# rover.net
KiCad netlist of a schematic drawn in EAGLE
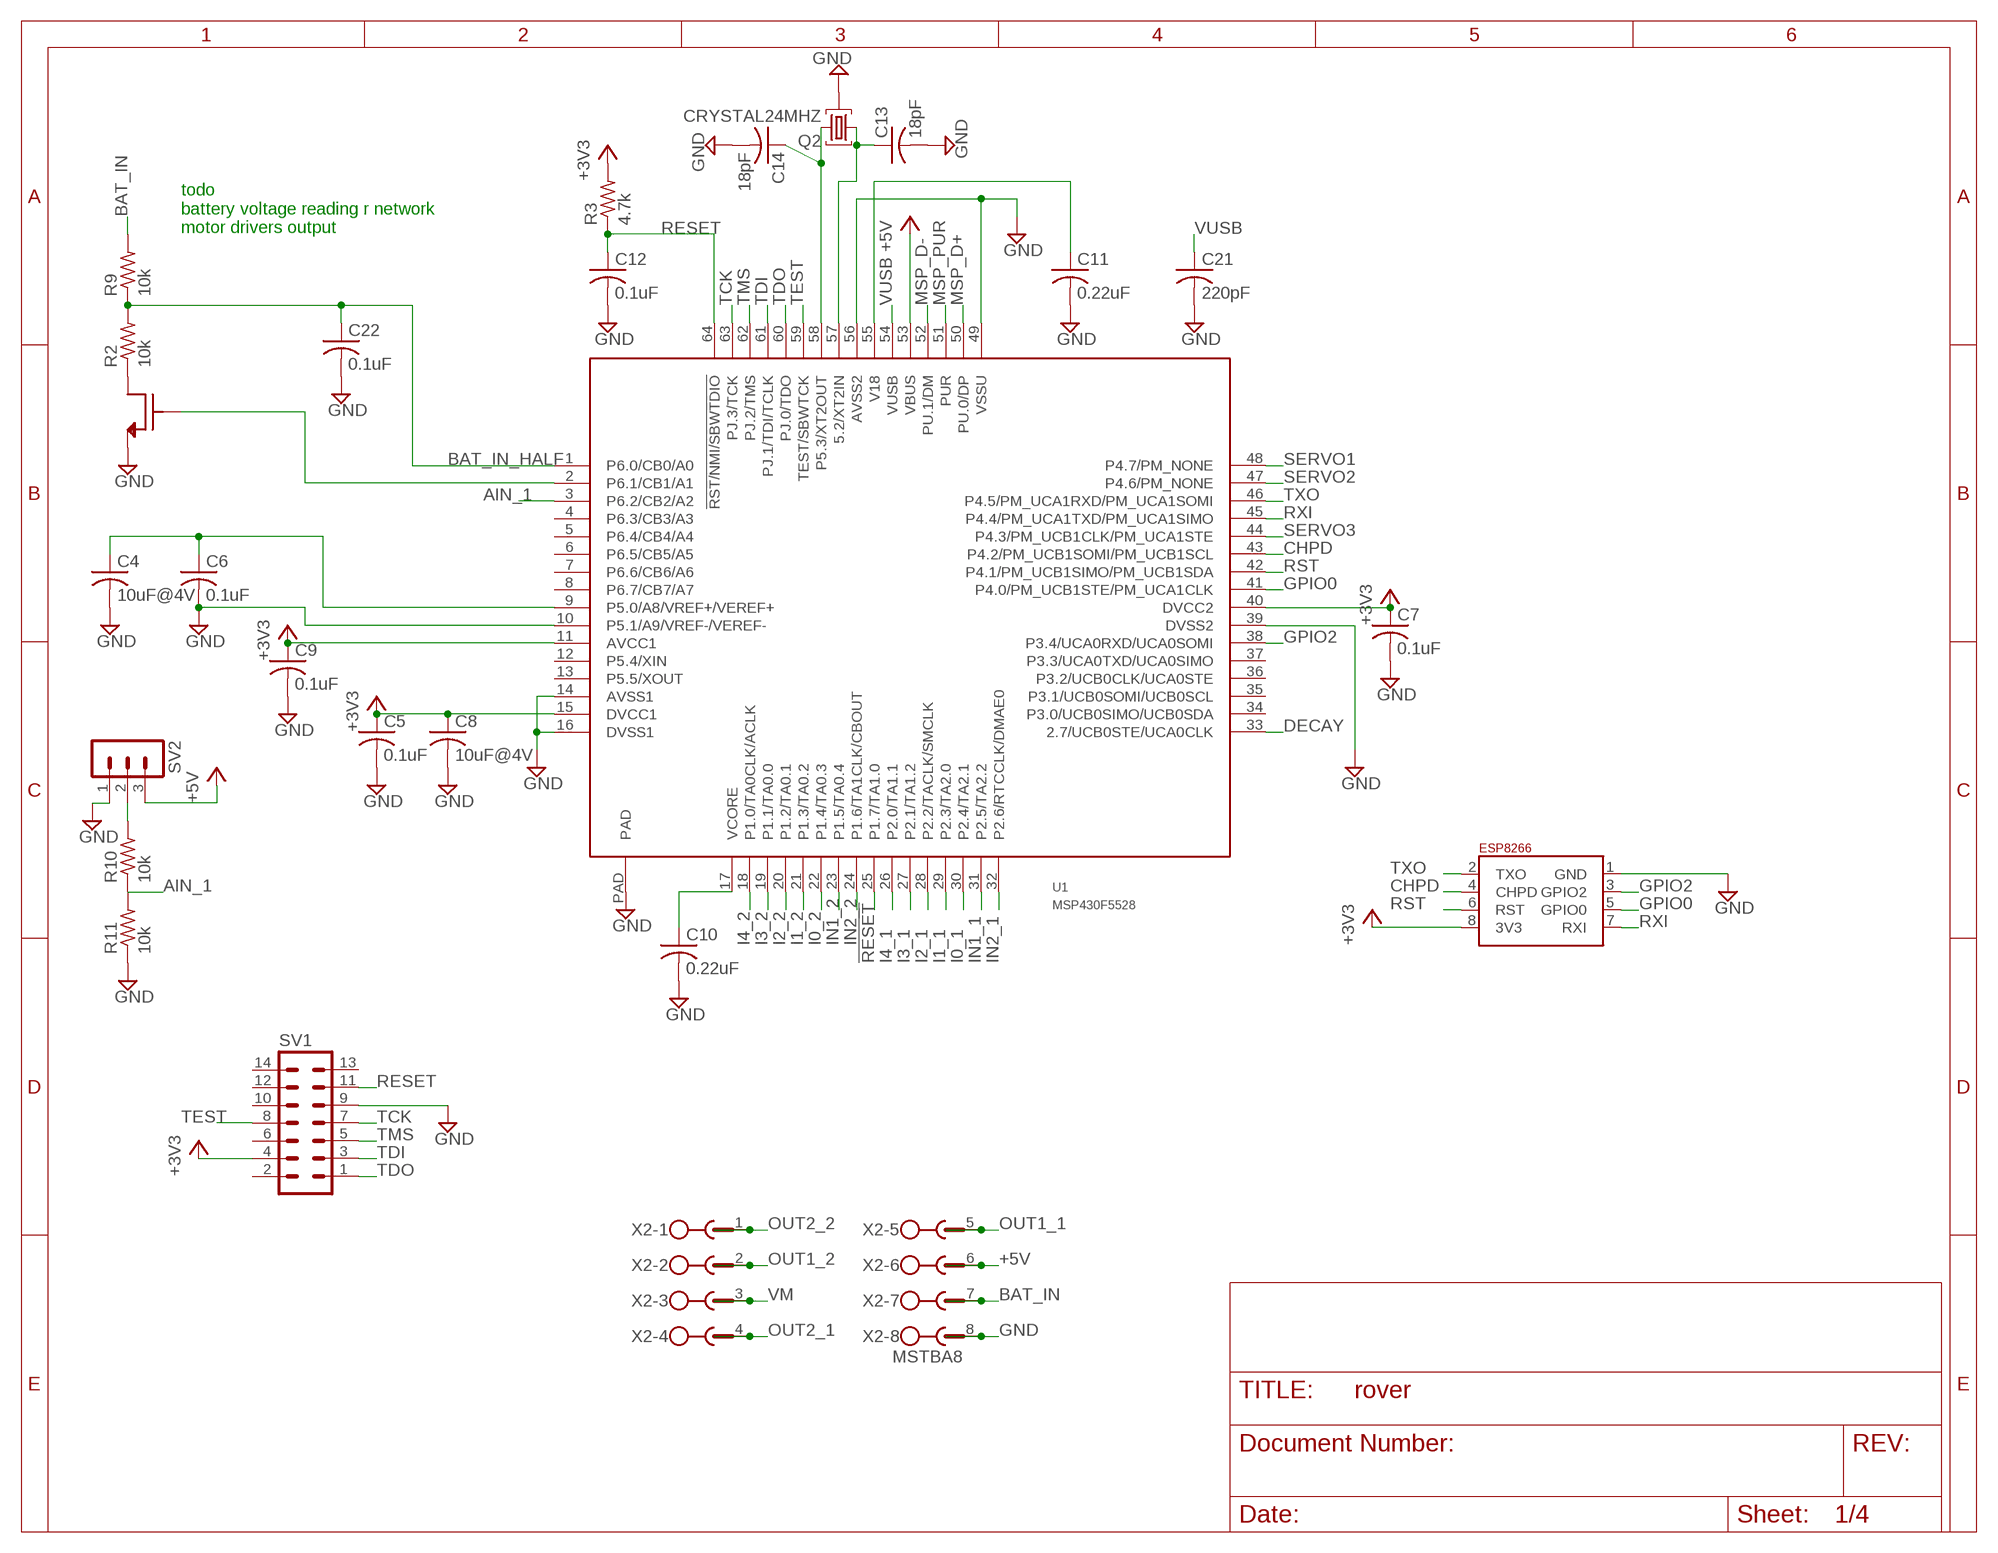
[diagram p0: schematic, sheet 1]
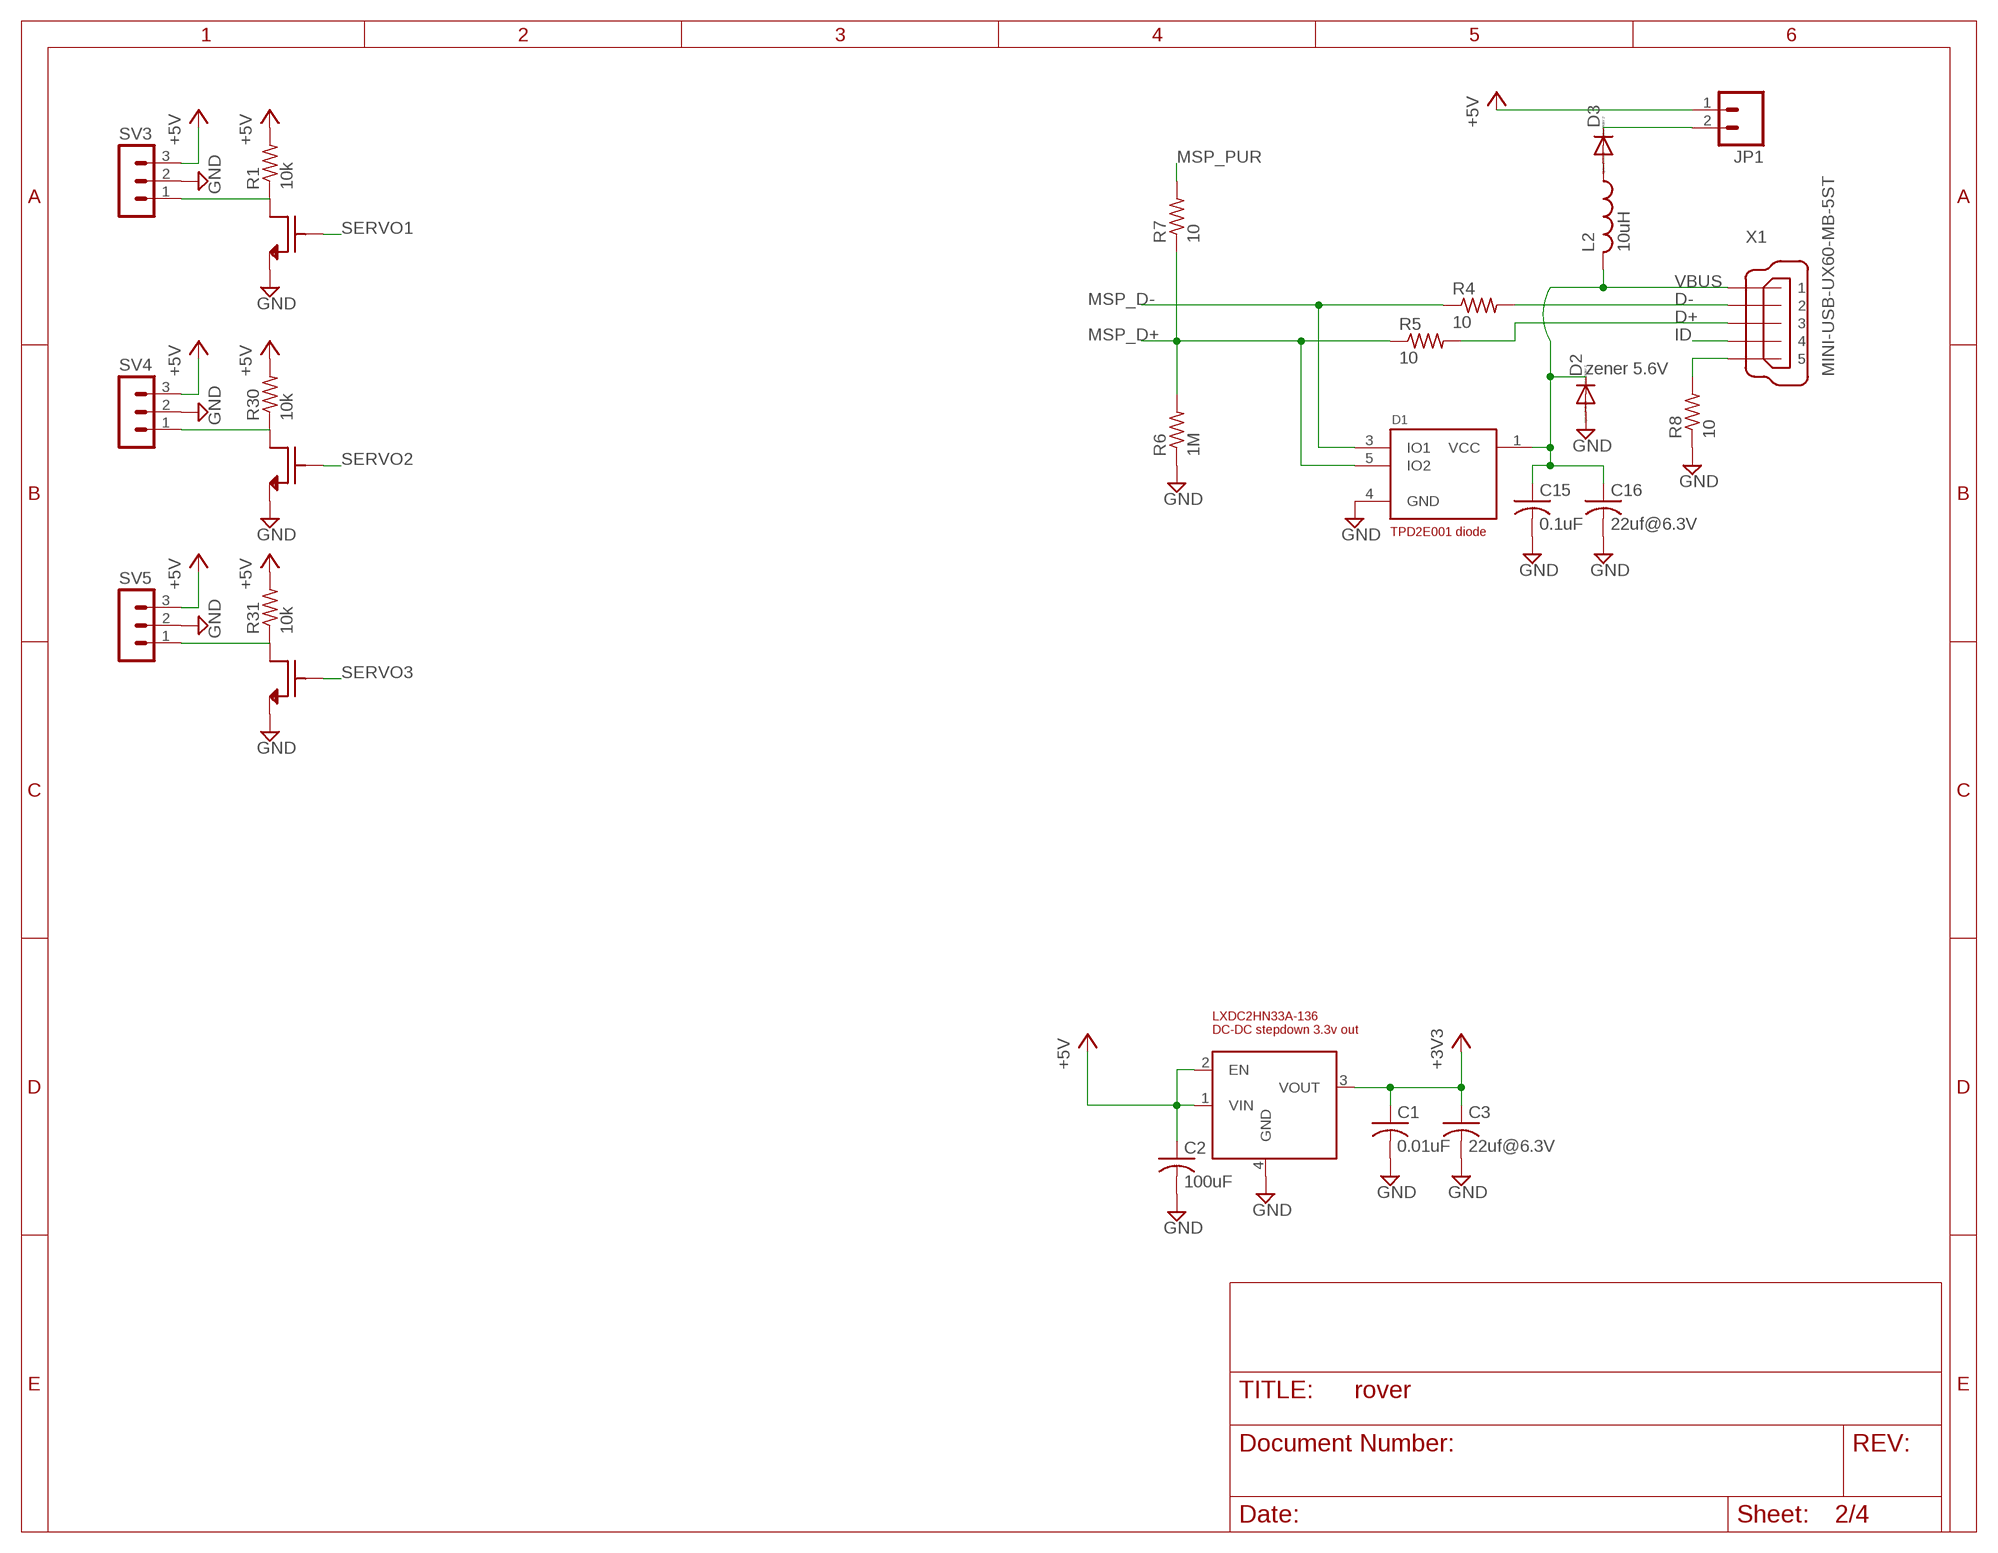
[diagram p1: schematic, sheet 2]
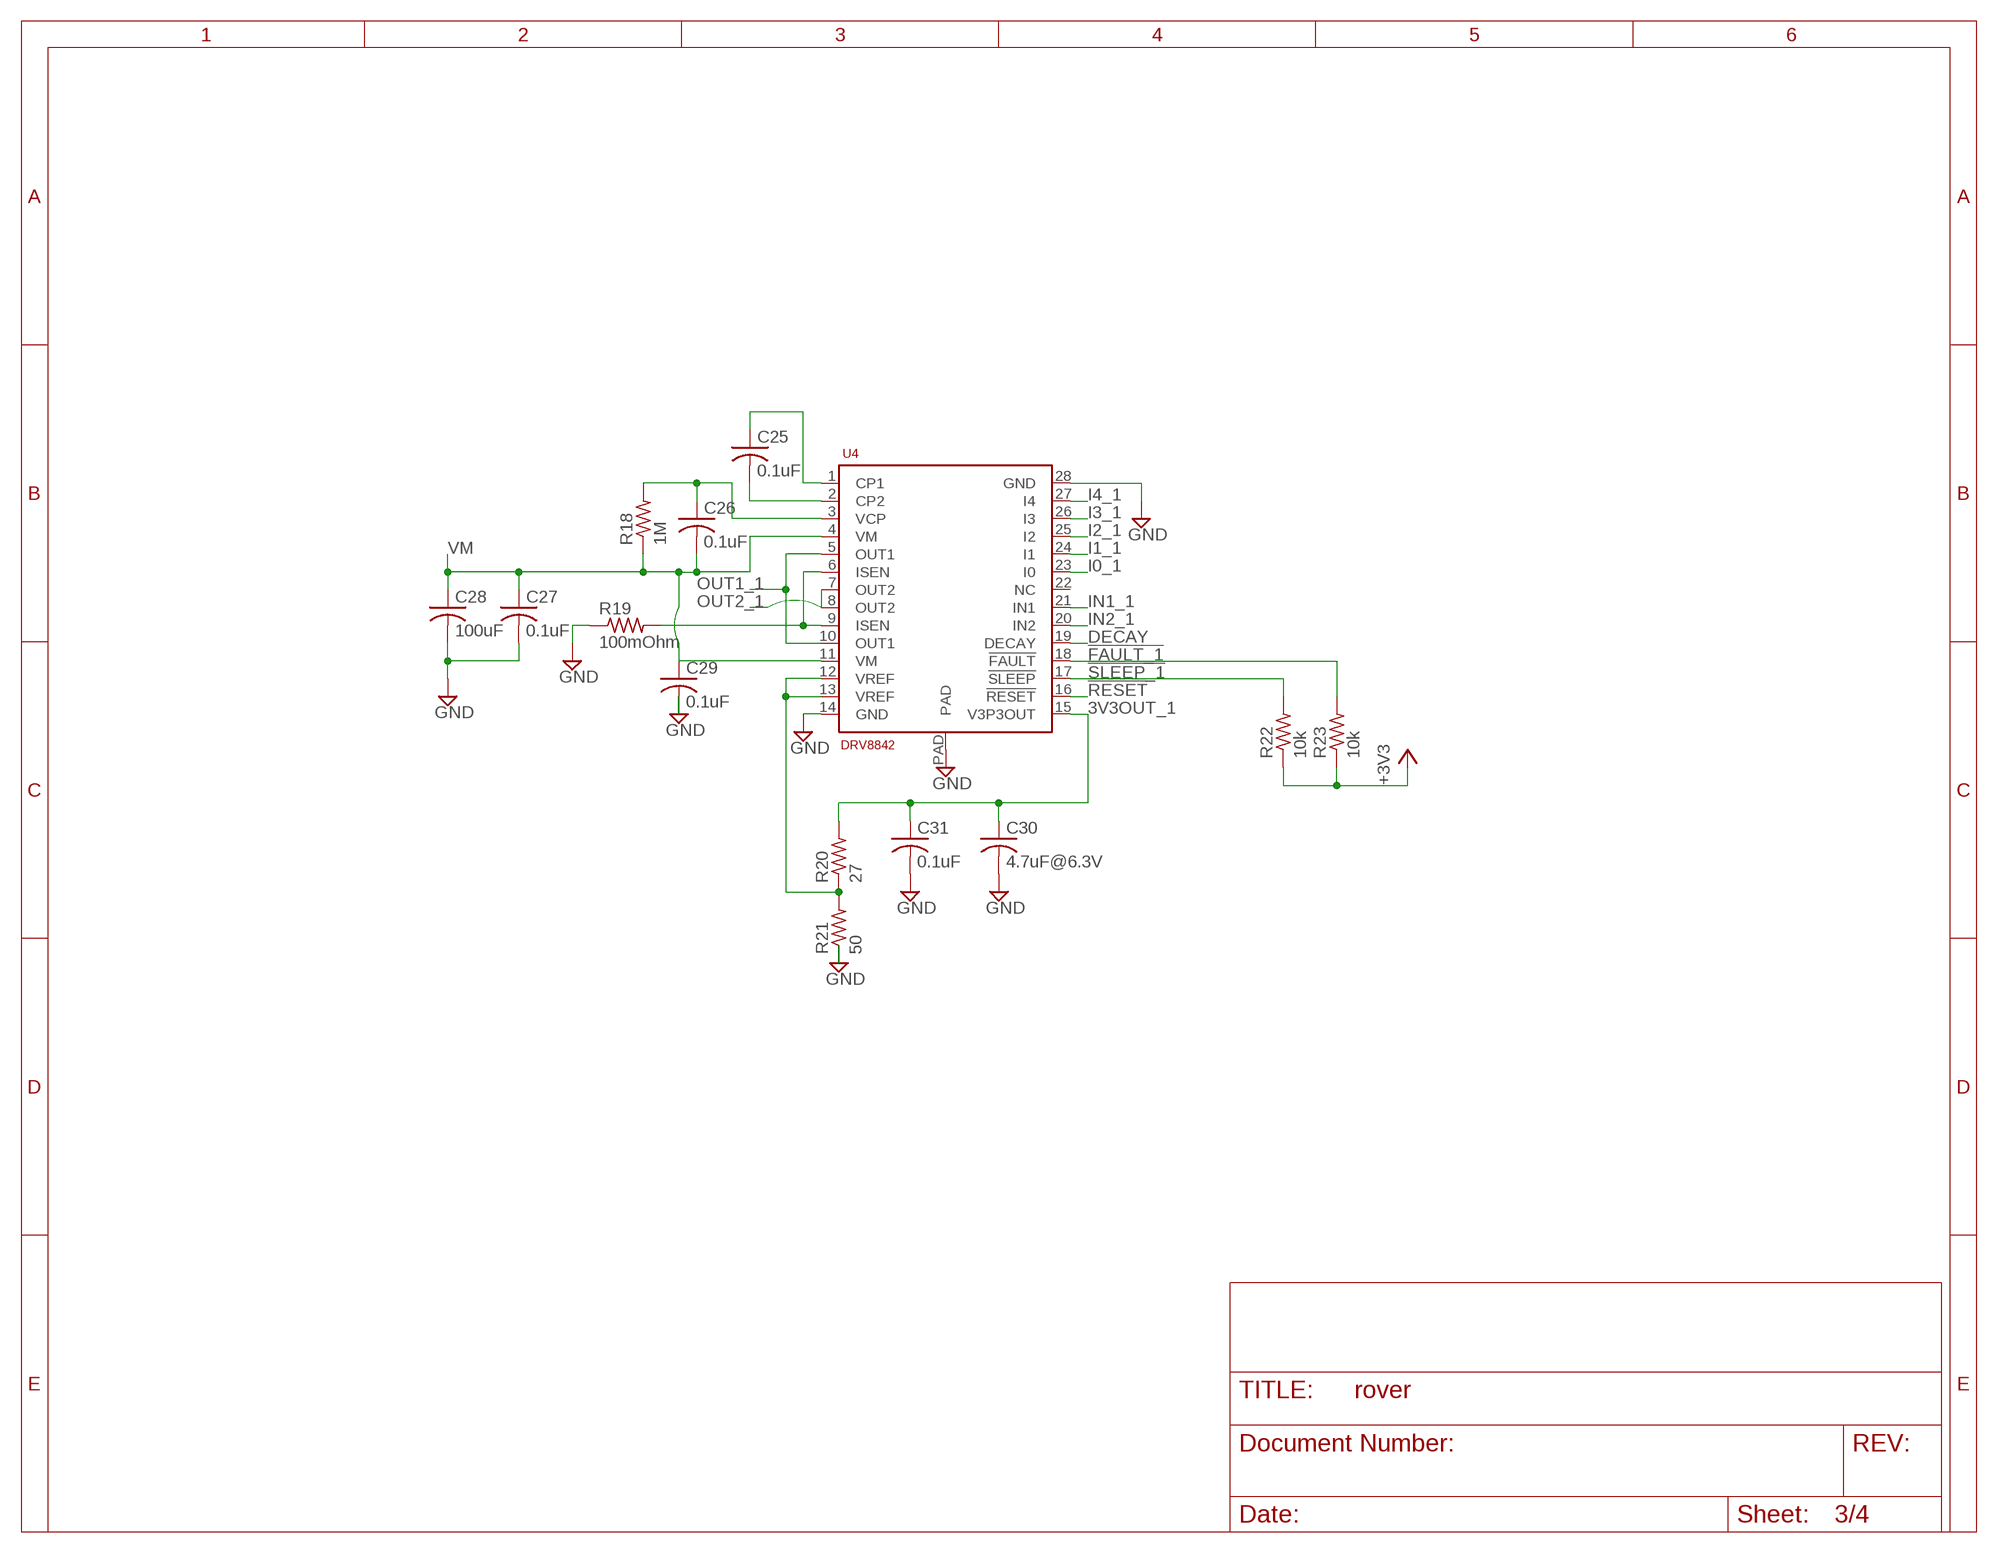
[diagram p2: schematic, sheet 3]
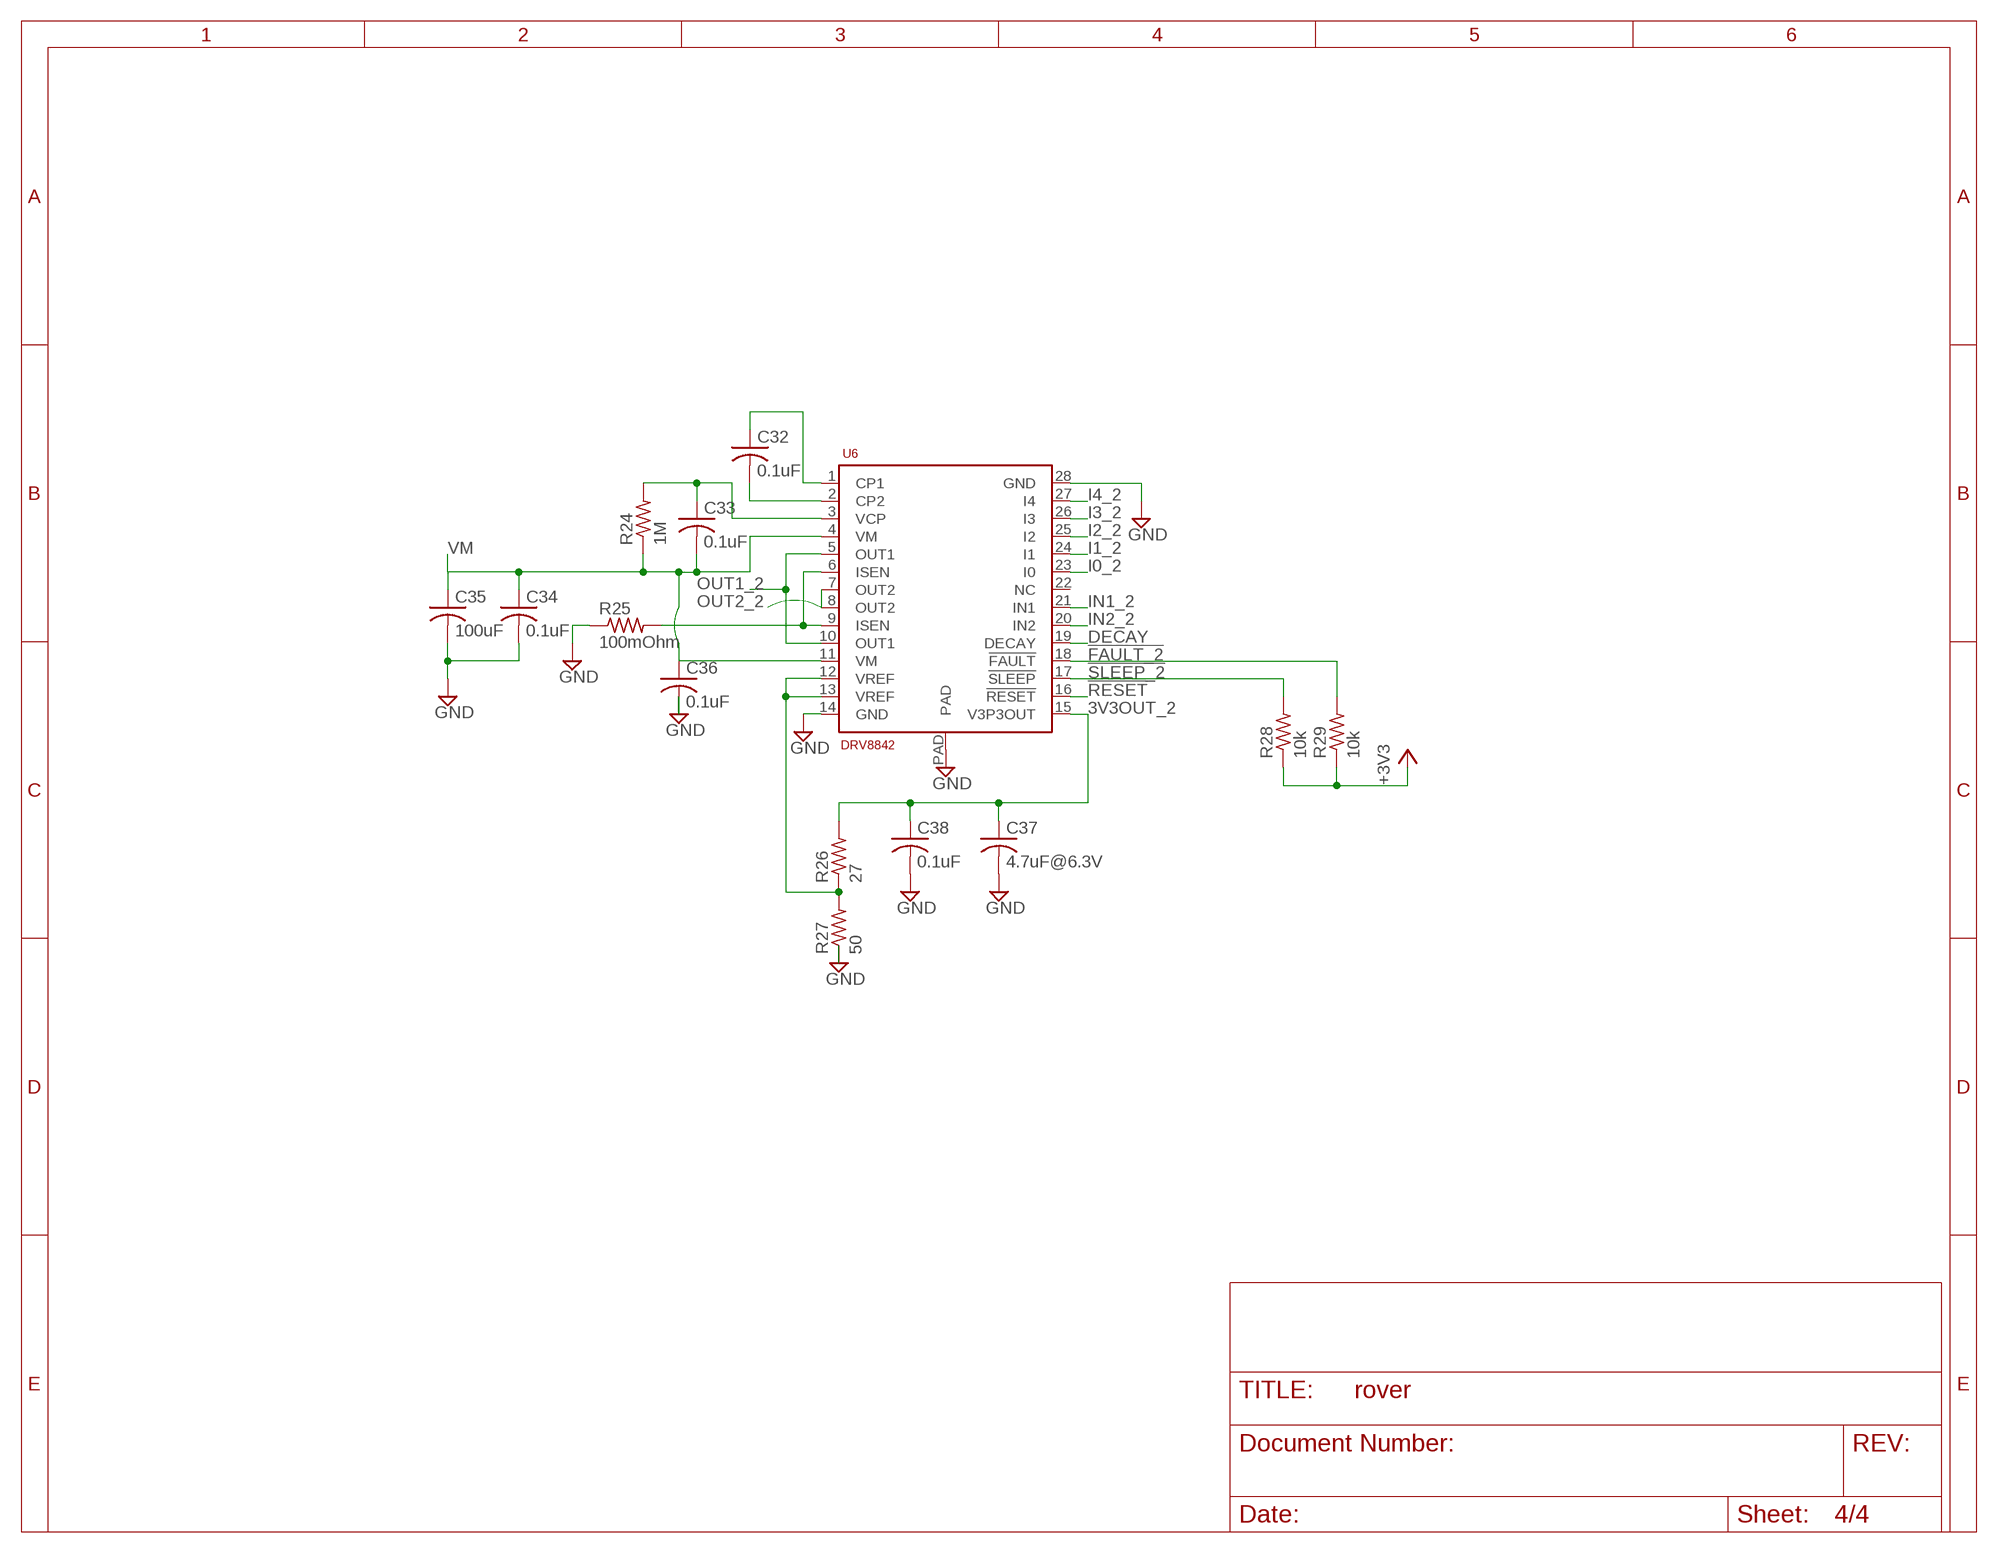
[diagram p3: schematic, sheet 4]

(export (version "E")
  (design (tool "Eeschema 10.0.6"))
  (components
    (comp (ref "C1")
      (value "0.01uF")
      (footprint "eagle-import:C0603")
      (fields (field (name "MFG") "murata") (field (name "MPN") "GRM1885C1H103JA01D"))
      (libsource (lib "eagle-import") (part "C-USC0603-0.01UF-"))
    )
    (comp (ref "C2")
      (value "100uF")
      (footprint "eagle-import:875105344010")
      (fields (field (name "MFG") "wurth") (field (name "MPN") "875105344010"))
      (libsource (lib "eagle-import") (part "C-US100UF"))
    )
    (comp (ref "C3")
      (value "22uf@6.3V")
      (footprint "eagle-import:C0603")
      (fields (field (name "MFG") "samsung") (field (name "MPN") "CL10A226MQ8NRNC"))
      (libsource (lib "eagle-import") (part "C-USC060322UF"))
    )
    (comp (ref "C15")
      (value "0.1uF")
      (footprint "eagle-import:C0603")
      (fields (field (name "MFG") "yageo") (field (name "MPN") "CC0603KRX7R7BB104"))
      (libsource (lib "eagle-import") (part "C-USC06030.1UF"))
    )
    (comp (ref "C16")
      (value "22uf@6.3V")
      (footprint "eagle-import:C0603")
      (fields (field (name "MFG") "samsung") (field (name "MPN") "CL10A226MQ8NRNC"))
      (libsource (lib "eagle-import") (part "C-USC060322UF"))
    )
    (comp (ref "D1")
      (value "USB-DIODE")
      (footprint "eagle-import:-DRL")
      (fields (field (name "MFG") "ti") (field (name "MPN") "TPD2E001DRLRG4"))
      (libsource (lib "eagle-import") (part "USB-DIODE"))
    )
    (comp (ref "D2")
      (value "zener 5.6V")
      (footprint "eagle-import:SOD123")
      (fields (field (name "MFG") "diodes inc") (field (name "MPN") " MMSZ5232B-7-F"))
      (libsource (lib "eagle-import") (part "DIODE-SOD123"))
    )
    (comp (ref "D3")
      (value "DIODE-")
      (footprint "eagle-import:DB2X20700L")
      (fields (field (name "MFG") "panasonic") (field (name "MPN") "DB2X20700L"))
      (libsource (lib "eagle-import") (part "DIODE-"))
    )
    (comp (ref "JP1")
      (value "M02PTH")
      (footprint "eagle-import:1X02")
      (libsource (lib "eagle-import") (part "M02PTH"))
    )
    (comp (ref "L2")
      (value "10uH")
      (footprint "eagle-import:VLS201610ET")
      (fields (field (name "MFG") "tdk") (field (name "MPN") " VLS201610ET-100M "))
      (libsource (lib "eagle-import") (part "L-USVLS201610ET-10UH-"))
    )
    (comp (ref "R1")
      (value "10k")
      (footprint "eagle-import:R0603")
      (fields (field (name "MFG") "yageo") (field (name "MPN") "RC0603JR-0710KL"))
      (libsource (lib "eagle-import") (part "R-US_R060310K"))
    )
    (comp (ref "R4")
      (value "10")
      (footprint "eagle-import:R0603")
      (fields (field (name "MFG") "panasonic") (field (name "MPN") "ERJ-3EKF10R0V "))
      (libsource (lib "eagle-import") (part "R-US_R060310"))
    )
    (comp (ref "R5")
      (value "10")
      (footprint "eagle-import:R0603")
      (fields (field (name "MFG") "panasonic") (field (name "MPN") "ERJ-3EKF10R0V "))
      (libsource (lib "eagle-import") (part "R-US_R060310"))
    )
    (comp (ref "R6")
      (value "1M")
      (footprint "eagle-import:R0603")
      (fields (field (name "MFG") "panasonic") (field (name "MPN") " ERJ-3EKF1004V "))
      (libsource (lib "eagle-import") (part "R-US_R06031M"))
    )
    (comp (ref "R7")
      (value "10")
      (footprint "eagle-import:R0603")
      (fields (field (name "MFG") "panasonic") (field (name "MPN") "ERJ-3EKF10R0V "))
      (libsource (lib "eagle-import") (part "R-US_R060310"))
    )
    (comp (ref "R8")
      (value "10")
      (footprint "eagle-import:R0603")
      (fields (field (name "MFG") "panasonic") (field (name "MPN") "ERJ-3EKF10R0V "))
      (libsource (lib "eagle-import") (part "R-US_R060310"))
    )
    (comp (ref "R30")
      (value "10k")
      (footprint "eagle-import:R0603")
      (fields (field (name "MFG") "yageo") (field (name "MPN") "RC0603JR-0710KL"))
      (libsource (lib "eagle-import") (part "R-US_R060310K"))
    )
    (comp (ref "R31")
      (value "10k")
      (footprint "eagle-import:R0603")
      (fields (field (name "MFG") "yageo") (field (name "MPN") "RC0603JR-0710KL"))
      (libsource (lib "eagle-import") (part "R-US_R060310K"))
    )
    (comp (ref "SV3")
      (value "MA03-1RND")
      (footprint "eagle-import:MA03-1-ROUND")
      (libsource (lib "eagle-import") (part "MA03-1RND"))
    )
    (comp (ref "SV4")
      (value "MA03-1RND")
      (footprint "eagle-import:MA03-1-ROUND")
      (libsource (lib "eagle-import") (part "MA03-1RND"))
    )
    (comp (ref "SV5")
      (value "MA03-1RND")
      (footprint "eagle-import:MA03-1-ROUND")
      (libsource (lib "eagle-import") (part "MA03-1RND"))
    )
    (comp (ref "U2")
      (value "LXDC2HN33A-136")
      (footprint "eagle-import:LXDC2HN33A-136")
      (fields (field (name "MFG") "murata"))
      (libsource (lib "eagle-import") (part "LXDC2HN33A-136"))
    )
    (comp (ref "U8")
      (value "NMOS2N7002P")
      (footprint "eagle-import:2N7002P-235")
      (fields (field (name "MFG") "nxp") (field (name "MPN") "2N7002P,235"))
      (libsource (lib "eagle-import") (part "NMOS2N7002P"))
    )
    (comp (ref "U9")
      (value "NMOS2N7002P")
      (footprint "eagle-import:2N7002P-235")
      (fields (field (name "MFG") "nxp") (field (name "MPN") "2N7002P,235"))
      (libsource (lib "eagle-import") (part "NMOS2N7002P"))
    )
    (comp (ref "U10")
      (value "NMOS2N7002P")
      (footprint "eagle-import:2N7002P-235")
      (fields (field (name "MFG") "nxp") (field (name "MPN") "2N7002P,235"))
      (libsource (lib "eagle-import") (part "NMOS2N7002P"))
    )
    (comp (ref "X1")
      (value "MINI-USB-UX60-MB-5ST")
      (footprint "eagle-import:UX60-MB-5ST")
      (fields (field (name "MFG") "Hirose") (field (name "MPN") "UX60-MB-5ST "))
      (libsource (lib "eagle-import") (part "MINI-USB-UX60-MB-5ST"))
    )
    (comp (ref "C25")
      (value "0.1uF")
      (footprint "eagle-import:C0603")
      (fields (field (name "MFG") "yageo") (field (name "MPN") "CC0603KRX7R7BB104"))
      (libsource (lib "eagle-import") (part "C-USC06030.1UF"))
    )
    (comp (ref "C26")
      (value "0.1uF")
      (footprint "eagle-import:C0603")
      (fields (field (name "MFG") "yageo") (field (name "MPN") "CC0603KRX7R7BB104"))
      (libsource (lib "eagle-import") (part "C-USC06030.1UF"))
    )
    (comp (ref "C27")
      (value "0.1uF")
      (footprint "eagle-import:C0603")
      (fields (field (name "MFG") "yageo") (field (name "MPN") "CC0603KRX7R7BB104"))
      (libsource (lib "eagle-import") (part "C-USC06030.1UF"))
    )
    (comp (ref "C28")
      (value "100uF")
      (footprint "eagle-import:875105344010")
      (fields (field (name "MFG") "wurth") (field (name "MPN") "875105344010"))
      (libsource (lib "eagle-import") (part "C-US100UF"))
    )
    (comp (ref "C29")
      (value "0.1uF")
      (footprint "eagle-import:C0603")
      (fields (field (name "MFG") "yageo") (field (name "MPN") "CC0603KRX7R7BB104"))
      (libsource (lib "eagle-import") (part "C-USC06030.1UF"))
    )
    (comp (ref "C30")
      (value "4.7uF@6.3V")
      (footprint "eagle-import:C0603")
      (fields (field (name "MFG") "samsung") (field (name "MPN") "CL10B475KQ8NQNC"))
      (libsource (lib "eagle-import") (part "C-USC06034.7UF"))
    )
    (comp (ref "C31")
      (value "0.1uF")
      (footprint "eagle-import:C0603")
      (fields (field (name "MFG") "yageo") (field (name "MPN") "CC0603KRX7R7BB104"))
      (libsource (lib "eagle-import") (part "C-USC06030.1UF"))
    )
    (comp (ref "R18")
      (value "1M")
      (footprint "eagle-import:R0603")
      (fields (field (name "MFG") "panasonic") (field (name "MPN") " ERJ-3EKF1004V "))
      (libsource (lib "eagle-import") (part "R-US_R06031M"))
    )
    (comp (ref "R19")
      (value "100mOhm")
      (footprint "eagle-import:R0603")
      (fields (field (name "MFG") "samsung") (field (name "MPN") "RU1608FR100CS"))
      (libsource (lib "eagle-import") (part "R-US_R0603100MILI"))
    )
    (comp (ref "R20")
      (value "27")
      (footprint "eagle-import:R0603")
      (fields (field (name "MFG") "yageo") (field (name "MPN") "RC0603FR-0727RL"))
      (libsource (lib "eagle-import") (part "R-US_R060327"))
    )
    (comp (ref "R21")
      (value "50")
      (footprint "eagle-import:R0603")
      (fields (field (name "MFG") "vishay") (field (name "MPN") "FC0603E50R0BST1"))
      (libsource (lib "eagle-import") (part "R-US_R060350"))
    )
    (comp (ref "R22")
      (value "10k")
      (footprint "eagle-import:R0603")
      (fields (field (name "MFG") "yageo") (field (name "MPN") "RC0603JR-0710KL"))
      (libsource (lib "eagle-import") (part "R-US_R060310K"))
    )
    (comp (ref "R23")
      (value "10k")
      (footprint "eagle-import:R0603")
      (fields (field (name "MFG") "yageo") (field (name "MPN") "RC0603JR-0710KL"))
      (libsource (lib "eagle-import") (part "R-US_R060310K"))
    )
    (comp (ref "U4")
      (value "DRV8842")
      (footprint "eagle-import:-PWP")
      (fields (field (name "MFG") "TI") (field (name "MPN") "DRV8842PWPR"))
      (libsource (lib "eagle-import") (part "DRV8842"))
    )
    (comp (ref "C4")
      (value "10uF@4V")
      (footprint "eagle-import:C0603")
      (fields (field (name "MFG") "murata") (field (name "MPN") "GRM188R60G106ME47D"))
      (libsource (lib "eagle-import") (part "C-USC060310UF"))
    )
    (comp (ref "C5")
      (value "0.1uF")
      (footprint "eagle-import:C0603")
      (fields (field (name "MFG") "yageo") (field (name "MPN") "CC0603KRX7R7BB104"))
      (libsource (lib "eagle-import") (part "C-USC06030.1UF"))
    )
    (comp (ref "C6")
      (value "0.1uF")
      (footprint "eagle-import:C0603")
      (fields (field (name "MFG") "yageo") (field (name "MPN") "CC0603KRX7R7BB104"))
      (libsource (lib "eagle-import") (part "C-USC06030.1UF"))
    )
    (comp (ref "C7")
      (value "0.1uF")
      (footprint "eagle-import:C0603")
      (fields (field (name "MFG") "yageo") (field (name "MPN") "CC0603KRX7R7BB104"))
      (libsource (lib "eagle-import") (part "C-USC06030.1UF"))
    )
    (comp (ref "C8")
      (value "10uF@4V")
      (footprint "eagle-import:C0603")
      (fields (field (name "MFG") "murata") (field (name "MPN") "GRM188R60G106ME47D"))
      (libsource (lib "eagle-import") (part "C-USC060310UF"))
    )
    (comp (ref "C9")
      (value "0.1uF")
      (footprint "eagle-import:C0603")
      (fields (field (name "MFG") "yageo") (field (name "MPN") "CC0603KRX7R7BB104"))
      (libsource (lib "eagle-import") (part "C-USC06030.1UF"))
    )
    (comp (ref "C10")
      (value "0.22uF")
      (footprint "eagle-import:C0603")
      (fields (field (name "MFG") "samsung") (field (name "MPN") "CL10B224KO8NNNC"))
      (libsource (lib "eagle-import") (part "C-USC06030.22UF"))
    )
    (comp (ref "C11")
      (value "0.22uF")
      (footprint "eagle-import:C0603")
      (fields (field (name "MFG") "samsung") (field (name "MPN") "CL10B224KO8NNNC"))
      (libsource (lib "eagle-import") (part "C-USC06030.22UF"))
    )
    (comp (ref "C12")
      (value "0.1uF")
      (footprint "eagle-import:C0603")
      (fields (field (name "MFG") "yageo") (field (name "MPN") "CC0603KRX7R7BB104"))
      (libsource (lib "eagle-import") (part "C-USC06030.1UF"))
    )
    (comp (ref "C13")
      (value "18pF")
      (footprint "eagle-import:C0603")
      (fields (field (name "MFG") "panasonic") (field (name "MPN") "CL10C180JB8NNNC"))
      (libsource (lib "eagle-import") (part "C-USC060318PF"))
    )
    (comp (ref "C14")
      (value "18pF")
      (footprint "eagle-import:C0603")
      (fields (field (name "MFG") "panasonic") (field (name "MPN") "CL10C180JB8NNNC"))
      (libsource (lib "eagle-import") (part "C-USC060318PF"))
    )
    (comp (ref "C21")
      (value "220pF")
      (footprint "eagle-import:C0603")
      (fields (field (name "MFG") "murata") (field (name "MPN") "GRM1885C1H221JA01D"))
      (libsource (lib "eagle-import") (part "C-USC0603-220PF-"))
    )
    (comp (ref "C22")
      (value "0.1uF")
      (footprint "eagle-import:C0603")
      (fields (field (name "MFG") "yageo") (field (name "MPN") "CC0603KRX7R7BB104"))
      (libsource (lib "eagle-import") (part "C-USC06030.1UF"))
    )
    (comp (ref "Q2")
      (value "CRYSTAL24MHZ")
      (footprint "eagle-import:ABM8")
      (fields (field (name "MFG") "Abracon") (field (name "MPN") "ABM8-24.000MHZ-B2-T "))
      (libsource (lib "eagle-import") (part "CRYSTAL24MHZ"))
    )
    (comp (ref "R2")
      (value "10k")
      (footprint "eagle-import:R0603")
      (fields (field (name "MFG") "yageo") (field (name "MPN") "RC0603JR-0710KL"))
      (libsource (lib "eagle-import") (part "R-US_R060310K"))
    )
    (comp (ref "R3")
      (value "4.7k")
      (footprint "eagle-import:R0603")
      (fields (field (name "MFG") "panasonic") (field (name "MPN") " ERJ-3GEYJ472V "))
      (libsource (lib "eagle-import") (part "R-US_R06034.7K"))
    )
    (comp (ref "R9")
      (value "10k")
      (footprint "eagle-import:R0603")
      (fields (field (name "MFG") "yageo") (field (name "MPN") "RC0603JR-0710KL"))
      (libsource (lib "eagle-import") (part "R-US_R060310K"))
    )
    (comp (ref "R10")
      (value "10k")
      (footprint "eagle-import:R0603")
      (fields (field (name "MFG") "yageo") (field (name "MPN") "RC0603JR-0710KL"))
      (libsource (lib "eagle-import") (part "R-US_R060310K"))
    )
    (comp (ref "R11")
      (value "10k")
      (footprint "eagle-import:R0603")
      (fields (field (name "MFG") "yageo") (field (name "MPN") "RC0603JR-0710KL"))
      (libsource (lib "eagle-import") (part "R-US_R060310K"))
    )
    (comp (ref "SV1")
      (value "MA07-2THM")
      (footprint "eagle-import:MA07-2")
      (libsource (lib "eagle-import") (part "MA07-2THM"))
    )
    (comp (ref "SV2")
      (value "MA03-1RND")
      (footprint "eagle-import:MA03-1-ROUND")
      (libsource (lib "eagle-import") (part "MA03-1RND"))
    )
    (comp (ref "U1")
      (value "MSP430F5528")
      (footprint "eagle-import:-RGC-N64")
      (fields (field (name "MFG") "TI") (field (name "MPN") "MSP430F5528IRGCR"))
      (libsource (lib "eagle-import") (part "MSP430F5528"))
    )
    (comp (ref "U3")
      (value "NMOS2N7002P")
      (footprint "eagle-import:2N7002P-235")
      (fields (field (name "MFG") "nxp") (field (name "MPN") "2N7002P,235"))
      (libsource (lib "eagle-import") (part "NMOS2N7002P"))
    )
    (comp (ref "U15")
      (value "ESP8266")
      (footprint "eagle-import:ESP8266")
      (fields (field (name "MFG") "expressive") (field (name "MPN") "esp8266"))
      (libsource (lib "eagle-import") (part "ESP8266"))
    )
    (comp (ref "X2")
      (value "MSTBA8")
      (footprint "eagle-import:MSTBA8")
      (fields (field (name "MF") "FARNELL") (field (name "MFG") "Phoenix") (field (name "MPN") "1757307"))
      (libsource (lib "eagle-import") (part "MSTBA8"))
    )
    (comp (ref "C32")
      (value "0.1uF")
      (footprint "eagle-import:C0603")
      (fields (field (name "MFG") "yageo") (field (name "MPN") "CC0603KRX7R7BB104"))
      (libsource (lib "eagle-import") (part "C-USC06030.1UF"))
    )
    (comp (ref "C33")
      (value "0.1uF")
      (footprint "eagle-import:C0603")
      (fields (field (name "MFG") "yageo") (field (name "MPN") "CC0603KRX7R7BB104"))
      (libsource (lib "eagle-import") (part "C-USC06030.1UF"))
    )
    (comp (ref "C34")
      (value "0.1uF")
      (footprint "eagle-import:C0603")
      (fields (field (name "MFG") "yageo") (field (name "MPN") "CC0603KRX7R7BB104"))
      (libsource (lib "eagle-import") (part "C-USC06030.1UF"))
    )
    (comp (ref "C35")
      (value "100uF")
      (footprint "eagle-import:875105344010")
      (fields (field (name "MFG") "wurth") (field (name "MPN") "875105344010"))
      (libsource (lib "eagle-import") (part "C-US100UF"))
    )
    (comp (ref "C36")
      (value "0.1uF")
      (footprint "eagle-import:C0603")
      (fields (field (name "MFG") "yageo") (field (name "MPN") "CC0603KRX7R7BB104"))
      (libsource (lib "eagle-import") (part "C-USC06030.1UF"))
    )
    (comp (ref "C37")
      (value "4.7uF@6.3V")
      (footprint "eagle-import:C0603")
      (fields (field (name "MFG") "samsung") (field (name "MPN") "CL10B475KQ8NQNC"))
      (libsource (lib "eagle-import") (part "C-USC06034.7UF"))
    )
    (comp (ref "C38")
      (value "0.1uF")
      (footprint "eagle-import:C0603")
      (fields (field (name "MFG") "yageo") (field (name "MPN") "CC0603KRX7R7BB104"))
      (libsource (lib "eagle-import") (part "C-USC06030.1UF"))
    )
    (comp (ref "R24")
      (value "1M")
      (footprint "eagle-import:R0603")
      (fields (field (name "MFG") "panasonic") (field (name "MPN") " ERJ-3EKF1004V "))
      (libsource (lib "eagle-import") (part "R-US_R06031M"))
    )
    (comp (ref "R25")
      (value "100mOhm")
      (footprint "eagle-import:R0603")
      (fields (field (name "MFG") "samsung") (field (name "MPN") "RU1608FR100CS"))
      (libsource (lib "eagle-import") (part "R-US_R0603100MILI"))
    )
    (comp (ref "R26")
      (value "27")
      (footprint "eagle-import:R0603")
      (fields (field (name "MFG") "yageo") (field (name "MPN") "RC0603FR-0727RL"))
      (libsource (lib "eagle-import") (part "R-US_R060327"))
    )
    (comp (ref "R27")
      (value "50")
      (footprint "eagle-import:R0603")
      (fields (field (name "MFG") "vishay") (field (name "MPN") "FC0603E50R0BST1"))
      (libsource (lib "eagle-import") (part "R-US_R060350"))
    )
    (comp (ref "R28")
      (value "10k")
      (footprint "eagle-import:R0603")
      (fields (field (name "MFG") "yageo") (field (name "MPN") "RC0603JR-0710KL"))
      (libsource (lib "eagle-import") (part "R-US_R060310K"))
    )
    (comp (ref "R29")
      (value "10k")
      (footprint "eagle-import:R0603")
      (fields (field (name "MFG") "yageo") (field (name "MPN") "RC0603JR-0710KL"))
      (libsource (lib "eagle-import") (part "R-US_R060310K"))
    )
    (comp (ref "U6")
      (value "DRV8842")
      (footprint "eagle-import:-PWP")
      (fields (field (name "MFG") "TI") (field (name "MPN") "DRV8842PWPR"))
      (libsource (lib "eagle-import") (part "DRV8842"))
    )
  )
  (nets
    (net (code "1") (name "+3V3") (class "Default")
      (node (ref "C1") (pin "1") (pinfunction "1_1") (pintype "passive"))
      (node (ref "C3") (pin "1") (pinfunction "1_1") (pintype "passive"))
      (node (ref "C5") (pin "1") (pinfunction "1_1") (pintype "passive"))
      (node (ref "C7") (pin "1") (pinfunction "1_1") (pintype "passive"))
      (node (ref "C8") (pin "1") (pinfunction "1_1") (pintype "passive"))
      (node (ref "C9") (pin "1") (pinfunction "1_1") (pintype "passive"))
      (node (ref "R22") (pin "1") (pinfunction "1_1") (pintype "passive"))
      (node (ref "R23") (pin "1") (pinfunction "1_1") (pintype "passive"))
      (node (ref "R28") (pin "1") (pinfunction "1_1") (pintype "passive"))
      (node (ref "R29") (pin "1") (pinfunction "1_1") (pintype "passive"))
      (node (ref "R3") (pin "2") (pinfunction "2_2") (pintype "passive"))
      (node (ref "SV1") (pin "4") (pinfunction "4_4") (pintype "passive"))
      (node (ref "U1") (pin "11") (pinfunction "AVCC1_11") (pintype "bidirectional"))
      (node (ref "U1") (pin "15") (pinfunction "DVCC1_15") (pintype "bidirectional"))
      (node (ref "U1") (pin "40") (pinfunction "DVCC2_40") (pintype "bidirectional"))
      (node (ref "U15") (pin "8") (pinfunction "3V3_8") (pintype "bidirectional"))
      (node (ref "U2") (pin "3") (pinfunction "VOUT_3") (pintype "bidirectional"))
    )
    (net (code "2") (name "+5V") (class "Default")
      (node (ref "C2") (pin "P$1") (pinfunction "1_P$1") (pintype "passive"))
      (node (ref "JP1") (pin "1") (pinfunction "1_1") (pintype "passive"))
      (node (ref "R1") (pin "2") (pinfunction "2_2") (pintype "passive"))
      (node (ref "R30") (pin "2") (pinfunction "2_2") (pintype "passive"))
      (node (ref "R31") (pin "2") (pinfunction "2_2") (pintype "passive"))
      (node (ref "SV2") (pin "3") (pinfunction "3_3") (pintype "passive"))
      (node (ref "SV3") (pin "3") (pinfunction "3_3") (pintype "passive"))
      (node (ref "SV4") (pin "3") (pinfunction "3_3") (pintype "passive"))
      (node (ref "SV5") (pin "3") (pinfunction "3_3") (pintype "passive"))
      (node (ref "U1") (pin "53") (pinfunction "VBUS_53") (pintype "bidirectional"))
      (node (ref "U2") (pin "1") (pinfunction "VIN_1") (pintype "bidirectional"))
      (node (ref "U2") (pin "2") (pinfunction "EN_2") (pintype "bidirectional"))
      (node (ref "X2") (pin "6") (pinfunction "1_6") (pintype "passive"))
    )
    (net (code "3") (name "3V3OUT_1") (class "Default")
      (node (ref "C30") (pin "1") (pinfunction "1_1") (pintype "passive"))
      (node (ref "C31") (pin "1") (pinfunction "1_1") (pintype "passive"))
      (node (ref "R20") (pin "2") (pinfunction "2_2") (pintype "passive"))
      (node (ref "U4") (pin "15") (pinfunction "V3P3OUT_15") (pintype "bidirectional"))
    )
    (net (code "4") (name "3V3OUT_2") (class "Default")
      (node (ref "C37") (pin "1") (pinfunction "1_1") (pintype "passive"))
      (node (ref "C38") (pin "1") (pinfunction "1_1") (pintype "passive"))
      (node (ref "R26") (pin "2") (pinfunction "2_2") (pintype "passive"))
      (node (ref "U6") (pin "15") (pinfunction "V3P3OUT_15") (pintype "bidirectional"))
    )
    (net (code "5") (name "AIN_1") (class "Default")
      (node (ref "R10") (pin "1") (pinfunction "1_1") (pintype "passive"))
      (node (ref "R11") (pin "2") (pinfunction "2_2") (pintype "passive"))
      (node (ref "U1") (pin "3") (pinfunction "P6.2/CB2/A2_3") (pintype "bidirectional"))
    )
    (net (code "6") (name "BAT_IN") (class "Default")
      (node (ref "R9") (pin "2") (pinfunction "2_2") (pintype "passive"))
      (node (ref "X2") (pin "7") (pinfunction "1_7") (pintype "passive"))
    )
    (net (code "7") (name "BAT_IN_HALF") (class "Default")
      (node (ref "C22") (pin "1") (pinfunction "1_1") (pintype "passive"))
      (node (ref "R2") (pin "2") (pinfunction "2_2") (pintype "passive"))
      (node (ref "R9") (pin "1") (pinfunction "1_1") (pintype "passive"))
      (node (ref "U1") (pin "1") (pinfunction "P6.0/CB0/A0_1") (pintype "bidirectional"))
    )
    (net (code "8") (name "CHPD") (class "Default")
      (node (ref "U1") (pin "43") (pinfunction "P4.2/PM_UCB1SOMI/PM_UCB1SCL_43") (pintype "bidirectional"))
      (node (ref "U15") (pin "4") (pinfunction "CHPD_4") (pintype "bidirectional"))
    )
    (net (code "9") (name "D+") (class "Default")
      (node (ref "R5") (pin "2") (pinfunction "2_2") (pintype "passive"))
      (node (ref "X1") (pin "3") (pinfunction "3_3") (pintype "input"))
    )
    (net (code "10") (name "D-") (class "Default")
      (node (ref "R4") (pin "2") (pinfunction "2_2") (pintype "passive"))
      (node (ref "X1") (pin "2") (pinfunction "2_2") (pintype "input"))
    )
    (net (code "11") (name "DECAY") (class "Default")
      (node (ref "U1") (pin "33") (pinfunction "2.7/UCB0STE/UCA0CLK_33") (pintype "bidirectional"))
      (node (ref "U4") (pin "19") (pinfunction "DECAY_19") (pintype "bidirectional"))
      (node (ref "U6") (pin "19") (pinfunction "DECAY_19") (pintype "bidirectional"))
    )
    (net (code "12") (name "GND") (class "Default")
      (node (ref "C1") (pin "2") (pinfunction "2_2") (pintype "passive"))
      (node (ref "C10") (pin "2") (pinfunction "2_2") (pintype "passive"))
      (node (ref "C11") (pin "2") (pinfunction "2_2") (pintype "passive"))
      (node (ref "C12") (pin "2") (pinfunction "2_2") (pintype "passive"))
      (node (ref "C13") (pin "2") (pinfunction "2_2") (pintype "passive"))
      (node (ref "C14") (pin "2") (pinfunction "2_2") (pintype "passive"))
      (node (ref "C15") (pin "2") (pinfunction "2_2") (pintype "passive"))
      (node (ref "C16") (pin "2") (pinfunction "2_2") (pintype "passive"))
      (node (ref "C2") (pin "P$2") (pinfunction "2_P$2") (pintype "passive"))
      (node (ref "C21") (pin "2") (pinfunction "2_2") (pintype "passive"))
      (node (ref "C22") (pin "2") (pinfunction "2_2") (pintype "passive"))
      (node (ref "C27") (pin "2") (pinfunction "2_2") (pintype "passive"))
      (node (ref "C28") (pin "P$2") (pinfunction "2_P$2") (pintype "passive"))
      (node (ref "C29") (pin "2") (pinfunction "2_2") (pintype "passive"))
      (node (ref "C3") (pin "2") (pinfunction "2_2") (pintype "passive"))
      (node (ref "C30") (pin "2") (pinfunction "2_2") (pintype "passive"))
      (node (ref "C31") (pin "2") (pinfunction "2_2") (pintype "passive"))
      (node (ref "C34") (pin "2") (pinfunction "2_2") (pintype "passive"))
      (node (ref "C35") (pin "P$2") (pinfunction "2_P$2") (pintype "passive"))
      (node (ref "C36") (pin "2") (pinfunction "2_2") (pintype "passive"))
      (node (ref "C37") (pin "2") (pinfunction "2_2") (pintype "passive"))
      (node (ref "C38") (pin "2") (pinfunction "2_2") (pintype "passive"))
      (node (ref "C4") (pin "2") (pinfunction "2_2") (pintype "passive"))
      (node (ref "C5") (pin "2") (pinfunction "2_2") (pintype "passive"))
      (node (ref "C6") (pin "2") (pinfunction "2_2") (pintype "passive"))
      (node (ref "C7") (pin "2") (pinfunction "2_2") (pintype "passive"))
      (node (ref "C8") (pin "2") (pinfunction "2_2") (pintype "passive"))
      (node (ref "C9") (pin "2") (pinfunction "2_2") (pintype "passive"))
      (node (ref "D1") (pin "4") (pinfunction "GND_4") (pintype "bidirectional"))
      (node (ref "D2") (pin "A") (pinfunction "A_A") (pintype "passive"))
      (node (ref "Q2") (pin "2") (pinfunction "2_2") (pintype "passive"))
      (node (ref "Q2") (pin "4") (pinfunction "2_4") (pintype "passive"))
      (node (ref "R11") (pin "1") (pinfunction "1_1") (pintype "passive"))
      (node (ref "R19") (pin "1") (pinfunction "1_1") (pintype "passive"))
      (node (ref "R21") (pin "1") (pinfunction "1_1") (pintype "passive"))
      (node (ref "R25") (pin "1") (pinfunction "1_1") (pintype "passive"))
      (node (ref "R27") (pin "1") (pinfunction "1_1") (pintype "passive"))
      (node (ref "R6") (pin "1") (pinfunction "1_1") (pintype "passive"))
      (node (ref "R8") (pin "1") (pinfunction "1_1") (pintype "passive"))
      (node (ref "SV1") (pin "9") (pinfunction "9_9") (pintype "passive"))
      (node (ref "SV2") (pin "1") (pinfunction "1_1") (pintype "passive"))
      (node (ref "SV3") (pin "2") (pinfunction "2_2") (pintype "passive"))
      (node (ref "SV4") (pin "2") (pinfunction "2_2") (pintype "passive"))
      (node (ref "SV5") (pin "2") (pinfunction "2_2") (pintype "passive"))
      (node (ref "U1") (pin "10") (pinfunction "P5.1/A9/VREF-/VEREF-_10") (pintype "bidirectional"))
      (node (ref "U1") (pin "14") (pinfunction "AVSS1_14") (pintype "bidirectional"))
      (node (ref "U1") (pin "16") (pinfunction "DVSS1_16") (pintype "bidirectional"))
      (node (ref "U1") (pin "39") (pinfunction "DVSS2_39") (pintype "bidirectional"))
      (node (ref "U1") (pin "49") (pinfunction "VSSU_49") (pintype "bidirectional"))
      (node (ref "U1") (pin "56") (pinfunction "AVSS2_56") (pintype "bidirectional"))
      (node (ref "U1") (pin "PAD") (pinfunction "PAD_PAD") (pintype "bidirectional"))
      (node (ref "U10") (pin "3") (pinfunction "D_3") (pintype "bidirectional"))
      (node (ref "U15") (pin "1") (pinfunction "GND_1") (pintype "bidirectional"))
      (node (ref "U2") (pin "4") (pinfunction "GND_4") (pintype "bidirectional"))
      (node (ref "U3") (pin "3") (pinfunction "D_3") (pintype "bidirectional"))
      (node (ref "U4") (pin "14") (pinfunction "GND_14") (pintype "bidirectional"))
      (node (ref "U4") (pin "28") (pinfunction "GND_28") (pintype "bidirectional"))
      (node (ref "U4") (pin "PAD") (pinfunction "PAD_PAD") (pintype "bidirectional"))
      (node (ref "U6") (pin "14") (pinfunction "GND_14") (pintype "bidirectional"))
      (node (ref "U6") (pin "28") (pinfunction "GND_28") (pintype "bidirectional"))
      (node (ref "U6") (pin "PAD") (pinfunction "PAD_PAD") (pintype "bidirectional"))
      (node (ref "U8") (pin "3") (pinfunction "D_3") (pintype "bidirectional"))
      (node (ref "U9") (pin "3") (pinfunction "D_3") (pintype "bidirectional"))
      (node (ref "X2") (pin "8") (pinfunction "1_8") (pintype "passive"))
    )
    (net (code "13") (name "GPIO0") (class "Default")
      (node (ref "U1") (pin "41") (pinfunction "P4.0/PM_UCB1STE/PM_UCA1CLK_41") (pintype "bidirectional"))
      (node (ref "U15") (pin "5") (pinfunction "GPIO0_5") (pintype "bidirectional"))
    )
    (net (code "14") (name "GPIO2") (class "Default")
      (node (ref "U1") (pin "38") (pinfunction "P3.4/UCA0RXD/UCA0SOMI_38") (pintype "bidirectional"))
      (node (ref "U15") (pin "3") (pinfunction "GPIO2_3") (pintype "bidirectional"))
    )
    (net (code "15") (name "I0_1") (class "Default")
      (node (ref "U1") (pin "30") (pinfunction "P2.4/TA2.1_30") (pintype "bidirectional"))
      (node (ref "U4") (pin "23") (pinfunction "I0_23") (pintype "bidirectional"))
    )
    (net (code "16") (name "I0_2") (class "Default")
      (node (ref "U1") (pin "22") (pinfunction "P1.4/TA0.3_22") (pintype "bidirectional"))
      (node (ref "U6") (pin "23") (pinfunction "I0_23") (pintype "bidirectional"))
    )
    (net (code "17") (name "I1_1") (class "Default")
      (node (ref "U1") (pin "29") (pinfunction "P2.3/TA2.0_29") (pintype "bidirectional"))
      (node (ref "U4") (pin "24") (pinfunction "I1_24") (pintype "bidirectional"))
    )
    (net (code "18") (name "I1_2") (class "Default")
      (node (ref "U1") (pin "21") (pinfunction "P1.3/TA0.2_21") (pintype "bidirectional"))
      (node (ref "U6") (pin "24") (pinfunction "I1_24") (pintype "bidirectional"))
    )
    (net (code "19") (name "I2_1") (class "Default")
      (node (ref "U1") (pin "28") (pinfunction "P2.2/TACLK/SMCLK_28") (pintype "bidirectional"))
      (node (ref "U4") (pin "25") (pinfunction "I2_25") (pintype "bidirectional"))
    )
    (net (code "20") (name "I2_2") (class "Default")
      (node (ref "U1") (pin "20") (pinfunction "P1.2/TA0.1_20") (pintype "bidirectional"))
      (node (ref "U6") (pin "25") (pinfunction "I2_25") (pintype "bidirectional"))
    )
    (net (code "21") (name "I3_1") (class "Default")
      (node (ref "U1") (pin "27") (pinfunction "P2.1/TA1.2_27") (pintype "bidirectional"))
      (node (ref "U4") (pin "26") (pinfunction "I3_26") (pintype "bidirectional"))
    )
    (net (code "22") (name "I3_2") (class "Default")
      (node (ref "U1") (pin "19") (pinfunction "P1.1/TA0.0_19") (pintype "bidirectional"))
      (node (ref "U6") (pin "26") (pinfunction "I3_26") (pintype "bidirectional"))
    )
    (net (code "23") (name "I4_1") (class "Default")
      (node (ref "U1") (pin "26") (pinfunction "P2.0/TA1.1_26") (pintype "bidirectional"))
      (node (ref "U4") (pin "27") (pinfunction "I4_27") (pintype "bidirectional"))
    )
    (net (code "24") (name "I4_2") (class "Default")
      (node (ref "U1") (pin "18") (pinfunction "P1.0/TA0CLK/ACLK_18") (pintype "bidirectional"))
      (node (ref "U6") (pin "27") (pinfunction "I4_27") (pintype "bidirectional"))
    )
    (net (code "25") (name "ID") (class "Default")
      (node (ref "X1") (pin "4") (pinfunction "4_4") (pintype "input"))
    )
    (net (code "26") (name "IN1_1") (class "Default")
      (node (ref "U1") (pin "31") (pinfunction "P2.5/TA2.2_31") (pintype "bidirectional"))
      (node (ref "U4") (pin "21") (pinfunction "IN1_21") (pintype "bidirectional"))
    )
    (net (code "27") (name "IN1_2") (class "Default")
      (node (ref "U1") (pin "23") (pinfunction "P1.5/TA0.4_23") (pintype "bidirectional"))
      (node (ref "U6") (pin "21") (pinfunction "IN1_21") (pintype "bidirectional"))
    )
    (net (code "28") (name "IN2_1") (class "Default")
      (node (ref "U1") (pin "32") (pinfunction "P2.6/RTCCLK/DMAE0_32") (pintype "bidirectional"))
      (node (ref "U4") (pin "20") (pinfunction "IN2_20") (pintype "bidirectional"))
    )
    (net (code "29") (name "IN2_2") (class "Default")
      (node (ref "U1") (pin "24") (pinfunction "P1.6/TA1CLK/CBOUT_24") (pintype "bidirectional"))
      (node (ref "U6") (pin "20") (pinfunction "IN2_20") (pintype "bidirectional"))
    )
    (net (code "30") (name "MSP_D+") (class "Default")
      (node (ref "D1") (pin "5") (pinfunction "IO2_5") (pintype "bidirectional"))
      (node (ref "R5") (pin "1") (pinfunction "1_1") (pintype "passive"))
      (node (ref "R6") (pin "2") (pinfunction "2_2") (pintype "passive"))
      (node (ref "R7") (pin "1") (pinfunction "1_1") (pintype "passive"))
      (node (ref "U1") (pin "50") (pinfunction "PU.0/DP_50") (pintype "bidirectional"))
    )
    (net (code "31") (name "MSP_D-") (class "Default")
      (node (ref "D1") (pin "3") (pinfunction "IO1_3") (pintype "bidirectional"))
      (node (ref "R4") (pin "1") (pinfunction "1_1") (pintype "passive"))
      (node (ref "U1") (pin "52") (pinfunction "PU.1/DM_52") (pintype "bidirectional"))
    )
    (net (code "32") (name "MSP_PUR") (class "Default")
      (node (ref "R7") (pin "2") (pinfunction "2_2") (pintype "passive"))
      (node (ref "U1") (pin "51") (pinfunction "PUR_51") (pintype "bidirectional"))
    )
    (net (code "33") (name "Net-(D3-A)") (class "Default")
      (node (ref "D3") (pin "P$1") (pinfunction "A_P$1") (pintype "passive"))
      (node (ref "L2") (pin "P$1") (pinfunction "1_P$1") (pintype "passive"))
    )
    (net (code "34") (name "Net-(D3-C)") (class "Default")
      (node (ref "D3") (pin "P$2") (pinfunction "C_P$2") (pintype "passive"))
      (node (ref "JP1") (pin "2") (pinfunction "2_2") (pintype "passive"))
    )
    (net (code "35") (name "Net-(R8-Pad2)") (class "Default")
      (node (ref "R8") (pin "2") (pinfunction "2_2") (pintype "passive"))
      (node (ref "X1") (pin "5") (pinfunction "5_5") (pintype "input"))
    )
    (net (code "36") (name "Net-(R10-Pad2)") (class "Default")
      (node (ref "R10") (pin "2") (pinfunction "2_2") (pintype "passive"))
      (node (ref "SV2") (pin "2") (pinfunction "2_2") (pintype "passive"))
    )
    (net (code "37") (name "Net-(R19-Pad2)") (class "Default")
      (node (ref "R19") (pin "2") (pinfunction "2_2") (pintype "passive"))
      (node (ref "U4") (pin "6") (pinfunction "ISEN_6") (pintype "bidirectional"))
      (node (ref "U4") (pin "9") (pinfunction "ISEN_9") (pintype "bidirectional"))
    )
    (net (code "38") (name "Net-(R20-Pad1)") (class "Default")
      (node (ref "R20") (pin "1") (pinfunction "1_1") (pintype "passive"))
      (node (ref "R21") (pin "2") (pinfunction "2_2") (pintype "passive"))
      (node (ref "U4") (pin "12") (pinfunction "VREF_12") (pintype "bidirectional"))
      (node (ref "U4") (pin "13") (pinfunction "VREF_13") (pintype "bidirectional"))
    )
    (net (code "39") (name "Net-(R25-Pad2)") (class "Default")
      (node (ref "R25") (pin "2") (pinfunction "2_2") (pintype "passive"))
      (node (ref "U6") (pin "6") (pinfunction "ISEN_6") (pintype "bidirectional"))
      (node (ref "U6") (pin "9") (pinfunction "ISEN_9") (pintype "bidirectional"))
    )
    (net (code "40") (name "Net-(R26-Pad1)") (class "Default")
      (node (ref "R26") (pin "1") (pinfunction "1_1") (pintype "passive"))
      (node (ref "R27") (pin "2") (pinfunction "2_2") (pintype "passive"))
      (node (ref "U6") (pin "12") (pinfunction "VREF_12") (pintype "bidirectional"))
      (node (ref "U6") (pin "13") (pinfunction "VREF_13") (pintype "bidirectional"))
    )
    (net (code "41") (name "Net-(U1-5.2{slash}XT2IN)") (class "Default")
      (node (ref "C13") (pin "1") (pinfunction "1_1") (pintype "passive"))
      (node (ref "Q2") (pin "1") (pinfunction "1_1") (pintype "passive"))
      (node (ref "U1") (pin "57") (pinfunction "5.2/XT2IN_57") (pintype "bidirectional"))
    )
    (net (code "42") (name "Net-(U1-P5.0{slash}A8{slash}VREF+{slash}VEREF+)") (class "Default")
      (node (ref "C4") (pin "1") (pinfunction "1_1") (pintype "passive"))
      (node (ref "C6") (pin "1") (pinfunction "1_1") (pintype "passive"))
      (node (ref "U1") (pin "9") (pinfunction "P5.0/A8/VREF+/VEREF+_9") (pintype "bidirectional"))
    )
    (net (code "43") (name "Net-(U1-P5.3{slash}XT2OUT)") (class "Default")
      (node (ref "C14") (pin "1") (pinfunction "1_1") (pintype "passive"))
      (node (ref "Q2") (pin "3") (pinfunction "3_3") (pintype "passive"))
      (node (ref "U1") (pin "58") (pinfunction "P5.3/XT2OUT_58") (pintype "bidirectional"))
    )
    (net (code "44") (name "Net-(U1-P6.1{slash}CB1{slash}A1)") (class "Default")
      (node (ref "U1") (pin "2") (pinfunction "P6.1/CB1/A1_2") (pintype "bidirectional"))
      (node (ref "U3") (pin "1") (pinfunction "G_1") (pintype "bidirectional"))
    )
    (net (code "45") (name "Net-(U1-V18)") (class "Default")
      (node (ref "C11") (pin "1") (pinfunction "1_1") (pintype "passive"))
      (node (ref "U1") (pin "55") (pinfunction "V18_55") (pintype "bidirectional"))
    )
    (net (code "46") (name "Net-(U1-VCORE)") (class "Default")
      (node (ref "C10") (pin "1") (pinfunction "1_1") (pintype "passive"))
      (node (ref "U1") (pin "17") (pinfunction "VCORE_17") (pintype "bidirectional"))
    )
    (net (code "47") (name "Net-(U3-S)") (class "Default")
      (node (ref "R2") (pin "1") (pinfunction "1_1") (pintype "passive"))
      (node (ref "U3") (pin "2") (pinfunction "S_2") (pintype "bidirectional"))
    )
    (net (code "48") (name "Net-(U4-CP1)") (class "Default")
      (node (ref "C25") (pin "1") (pinfunction "1_1") (pintype "passive"))
      (node (ref "U4") (pin "1") (pinfunction "CP1_1") (pintype "bidirectional"))
    )
    (net (code "49") (name "Net-(U4-CP2)") (class "Default")
      (node (ref "C25") (pin "2") (pinfunction "2_2") (pintype "passive"))
      (node (ref "U4") (pin "2") (pinfunction "CP2_2") (pintype "bidirectional"))
    )
    (net (code "50") (name "Net-(U4-VCP)") (class "Default")
      (node (ref "C26") (pin "1") (pinfunction "1_1") (pintype "passive"))
      (node (ref "R18") (pin "2") (pinfunction "2_2") (pintype "passive"))
      (node (ref "U4") (pin "3") (pinfunction "VCP_3") (pintype "bidirectional"))
    )
    (net (code "51") (name "Net-(U6-CP1)") (class "Default")
      (node (ref "C32") (pin "1") (pinfunction "1_1") (pintype "passive"))
      (node (ref "U6") (pin "1") (pinfunction "CP1_1") (pintype "bidirectional"))
    )
    (net (code "52") (name "Net-(U6-CP2)") (class "Default")
      (node (ref "C32") (pin "2") (pinfunction "2_2") (pintype "passive"))
      (node (ref "U6") (pin "2") (pinfunction "CP2_2") (pintype "bidirectional"))
    )
    (net (code "53") (name "Net-(U6-VCP)") (class "Default")
      (node (ref "C33") (pin "1") (pinfunction "1_1") (pintype "passive"))
      (node (ref "R24") (pin "2") (pinfunction "2_2") (pintype "passive"))
      (node (ref "U6") (pin "3") (pinfunction "VCP_3") (pintype "bidirectional"))
    )
    (net (code "54") (name "Net-(U8-S)") (class "Default")
      (node (ref "R1") (pin "1") (pinfunction "1_1") (pintype "passive"))
      (node (ref "SV3") (pin "1") (pinfunction "1_1") (pintype "passive"))
      (node (ref "U8") (pin "2") (pinfunction "S_2") (pintype "bidirectional"))
    )
    (net (code "55") (name "Net-(U9-S)") (class "Default")
      (node (ref "R30") (pin "1") (pinfunction "1_1") (pintype "passive"))
      (node (ref "SV4") (pin "1") (pinfunction "1_1") (pintype "passive"))
      (node (ref "U9") (pin "2") (pinfunction "S_2") (pintype "bidirectional"))
    )
    (net (code "56") (name "Net-(U10-S)") (class "Default")
      (node (ref "R31") (pin "1") (pinfunction "1_1") (pintype "passive"))
      (node (ref "SV5") (pin "1") (pinfunction "1_1") (pintype "passive"))
      (node (ref "U10") (pin "2") (pinfunction "S_2") (pintype "bidirectional"))
    )
    (net (code "57") (name "OUT1_1") (class "Default")
      (node (ref "U4") (pin "10") (pinfunction "OUT1_10") (pintype "bidirectional"))
      (node (ref "U4") (pin "5") (pinfunction "OUT1_5") (pintype "bidirectional"))
      (node (ref "X2") (pin "5") (pinfunction "1_5") (pintype "passive"))
    )
    (net (code "58") (name "OUT1_2") (class "Default")
      (node (ref "U6") (pin "10") (pinfunction "OUT1_10") (pintype "bidirectional"))
      (node (ref "U6") (pin "5") (pinfunction "OUT1_5") (pintype "bidirectional"))
      (node (ref "X2") (pin "2") (pinfunction "1_2") (pintype "passive"))
    )
    (net (code "59") (name "OUT2_1") (class "Default")
      (node (ref "U4") (pin "7") (pinfunction "OUT2_7") (pintype "bidirectional"))
      (node (ref "U4") (pin "8") (pinfunction "OUT2_8") (pintype "bidirectional"))
      (node (ref "X2") (pin "4") (pinfunction "1_4") (pintype "passive"))
    )
    (net (code "60") (name "OUT2_2") (class "Default")
      (node (ref "U6") (pin "7") (pinfunction "OUT2_7") (pintype "bidirectional"))
      (node (ref "U6") (pin "8") (pinfunction "OUT2_8") (pintype "bidirectional"))
      (node (ref "X2") (pin "1") (pinfunction "1_1") (pintype "passive"))
    )
    (net (code "61") (name "RESET") (class "Default")
      (node (ref "C12") (pin "1") (pinfunction "1_1") (pintype "passive"))
      (node (ref "R3") (pin "1") (pinfunction "1_1") (pintype "passive"))
      (node (ref "SV1") (pin "11") (pinfunction "11_11") (pintype "passive"))
      (node (ref "U1") (pin "64") (pinfunction "~{RST/NMI/SBWTDIO}_64") (pintype "bidirectional"))
    )
    (net (code "62") (name "RST") (class "Default")
      (node (ref "U1") (pin "42") (pinfunction "P4.1/PM_UCB1SIMO/PM_UCB1SDA_42") (pintype "bidirectional"))
      (node (ref "U15") (pin "6") (pinfunction "RST_6") (pintype "bidirectional"))
    )
    (net (code "63") (name "RXI") (class "Default")
      (node (ref "U1") (pin "45") (pinfunction "P4.4/PM_UCA1TXD/PM_UCA1SIMO_45") (pintype "bidirectional"))
      (node (ref "U15") (pin "7") (pinfunction "RXI_7") (pintype "bidirectional"))
    )
    (net (code "64") (name "SERVO1") (class "Default")
      (node (ref "U1") (pin "48") (pinfunction "P4.7/PM_NONE_48") (pintype "bidirectional"))
      (node (ref "U8") (pin "1") (pinfunction "G_1") (pintype "bidirectional"))
    )
    (net (code "65") (name "SERVO2") (class "Default")
      (node (ref "U1") (pin "47") (pinfunction "P4.6/PM_NONE_47") (pintype "bidirectional"))
      (node (ref "U9") (pin "1") (pinfunction "G_1") (pintype "bidirectional"))
    )
    (net (code "66") (name "SERVO3") (class "Default")
      (node (ref "U1") (pin "44") (pinfunction "P4.3/PM_UCB1CLK/PM_UCA1STE_44") (pintype "bidirectional"))
      (node (ref "U10") (pin "1") (pinfunction "G_1") (pintype "bidirectional"))
    )
    (net (code "67") (name "TCK") (class "Default")
      (node (ref "SV1") (pin "7") (pinfunction "7_7") (pintype "passive"))
      (node (ref "U1") (pin "63") (pinfunction "PJ.3/TCK_63") (pintype "bidirectional"))
    )
    (net (code "68") (name "TDI") (class "Default")
      (node (ref "SV1") (pin "3") (pinfunction "3_3") (pintype "passive"))
      (node (ref "U1") (pin "61") (pinfunction "PJ.1/TDI/TCLK_61") (pintype "bidirectional"))
    )
    (net (code "69") (name "TDO") (class "Default")
      (node (ref "SV1") (pin "1") (pinfunction "1_1") (pintype "passive"))
      (node (ref "U1") (pin "60") (pinfunction "PJ.0/TDO_60") (pintype "bidirectional"))
    )
    (net (code "70") (name "TEST") (class "Default")
      (node (ref "SV1") (pin "8") (pinfunction "8_8") (pintype "passive"))
      (node (ref "U1") (pin "59") (pinfunction "TEST/SBWTCK_59") (pintype "bidirectional"))
    )
    (net (code "71") (name "TMS") (class "Default")
      (node (ref "SV1") (pin "5") (pinfunction "5_5") (pintype "passive"))
      (node (ref "U1") (pin "62") (pinfunction "PJ.2/TMS_62") (pintype "bidirectional"))
    )
    (net (code "72") (name "TXO") (class "Default")
      (node (ref "U1") (pin "46") (pinfunction "P4.5/PM_UCA1RXD/PM_UCA1SOMI_46") (pintype "bidirectional"))
      (node (ref "U15") (pin "2") (pinfunction "TXO_2") (pintype "bidirectional"))
    )
    (net (code "73") (name "VBUS") (class "Default")
      (node (ref "C15") (pin "1") (pinfunction "1_1") (pintype "passive"))
      (node (ref "C16") (pin "1") (pinfunction "1_1") (pintype "passive"))
      (node (ref "D1") (pin "1") (pinfunction "VCC_1") (pintype "bidirectional"))
      (node (ref "D2") (pin "C") (pinfunction "C_C") (pintype "passive"))
      (node (ref "L2") (pin "P$2") (pinfunction "2_P$2") (pintype "passive"))
      (node (ref "X1") (pin "1") (pinfunction "1_1") (pintype "input"))
    )
    (net (code "74") (name "VM") (class "Default")
      (node (ref "C26") (pin "2") (pinfunction "2_2") (pintype "passive"))
      (node (ref "C27") (pin "1") (pinfunction "1_1") (pintype "passive"))
      (node (ref "C28") (pin "P$1") (pinfunction "1_P$1") (pintype "passive"))
      (node (ref "C29") (pin "1") (pinfunction "1_1") (pintype "passive"))
      (node (ref "C33") (pin "2") (pinfunction "2_2") (pintype "passive"))
      (node (ref "C34") (pin "1") (pinfunction "1_1") (pintype "passive"))
      (node (ref "C35") (pin "P$1") (pinfunction "1_P$1") (pintype "passive"))
      (node (ref "C36") (pin "1") (pinfunction "1_1") (pintype "passive"))
      (node (ref "R18") (pin "1") (pinfunction "1_1") (pintype "passive"))
      (node (ref "R24") (pin "1") (pinfunction "1_1") (pintype "passive"))
      (node (ref "U4") (pin "11") (pinfunction "VM_11") (pintype "bidirectional"))
      (node (ref "U4") (pin "4") (pinfunction "VM_4") (pintype "bidirectional"))
      (node (ref "U6") (pin "11") (pinfunction "VM_11") (pintype "bidirectional"))
      (node (ref "U6") (pin "4") (pinfunction "VM_4") (pintype "bidirectional"))
      (node (ref "X2") (pin "3") (pinfunction "1_3") (pintype "passive"))
    )
    (net (code "75") (name "VUSB") (class "Default")
      (node (ref "C21") (pin "1") (pinfunction "1_1") (pintype "passive"))
      (node (ref "U1") (pin "54") (pinfunction "VUSB_54") (pintype "bidirectional"))
    )
    (net (code "76") (name "unconnected-(SV1-Pad2)") (class "Default")
      (node (ref "SV1") (pin "2") (pinfunction "2_2") (pintype "passive"))
    )
    (net (code "77") (name "unconnected-(SV1-Pad6)") (class "Default")
      (node (ref "SV1") (pin "6") (pinfunction "6_6") (pintype "passive"))
    )
    (net (code "78") (name "unconnected-(SV1-Pad10)") (class "Default")
      (node (ref "SV1") (pin "10") (pinfunction "10_10") (pintype "passive"))
    )
    (net (code "79") (name "unconnected-(SV1-Pad12)") (class "Default")
      (node (ref "SV1") (pin "12") (pinfunction "12_12") (pintype "passive"))
    )
    (net (code "80") (name "unconnected-(SV1-Pad13)") (class "Default")
      (node (ref "SV1") (pin "13") (pinfunction "13_13") (pintype "passive"))
    )
    (net (code "81") (name "unconnected-(SV1-Pad14)") (class "Default")
      (node (ref "SV1") (pin "14") (pinfunction "14_14") (pintype "passive"))
    )
    (net (code "82") (name "unconnected-(U1-P3.0{slash}UCB0SIMO{slash}UCB0SDA-Pad34)") (class "Default")
      (node (ref "U1") (pin "34") (pinfunction "P3.0/UCB0SIMO/UCB0SDA_34") (pintype "bidirectional"))
    )
    (net (code "83") (name "unconnected-(U1-P3.1{slash}UCB0SOMI{slash}UCB0SCL-Pad35)") (class "Default")
      (node (ref "U1") (pin "35") (pinfunction "P3.1/UCB0SOMI/UCB0SCL_35") (pintype "bidirectional"))
    )
    (net (code "84") (name "unconnected-(U1-P3.2{slash}UCB0CLK{slash}UCA0STE-Pad36)") (class "Default")
      (node (ref "U1") (pin "36") (pinfunction "P3.2/UCB0CLK/UCA0STE_36") (pintype "bidirectional"))
    )
    (net (code "85") (name "unconnected-(U1-P3.3{slash}UCA0TXD{slash}UCA0SIMO-Pad37)") (class "Default")
      (node (ref "U1") (pin "37") (pinfunction "P3.3/UCA0TXD/UCA0SIMO_37") (pintype "bidirectional"))
    )
    (net (code "86") (name "unconnected-(U1-P5.4{slash}XIN-Pad12)") (class "Default")
      (node (ref "U1") (pin "12") (pinfunction "P5.4/XIN_12") (pintype "bidirectional"))
    )
    (net (code "87") (name "unconnected-(U1-P5.5{slash}XOUT-Pad13)") (class "Default")
      (node (ref "U1") (pin "13") (pinfunction "P5.5/XOUT_13") (pintype "bidirectional"))
    )
    (net (code "88") (name "unconnected-(U1-P6.3{slash}CB3{slash}A3-Pad4)") (class "Default")
      (node (ref "U1") (pin "4") (pinfunction "P6.3/CB3/A3_4") (pintype "bidirectional"))
    )
    (net (code "89") (name "unconnected-(U1-P6.4{slash}CB4{slash}A4-Pad5)") (class "Default")
      (node (ref "U1") (pin "5") (pinfunction "P6.4/CB4/A4_5") (pintype "bidirectional"))
    )
    (net (code "90") (name "unconnected-(U1-P6.5{slash}CB5{slash}A5-Pad6)") (class "Default")
      (node (ref "U1") (pin "6") (pinfunction "P6.5/CB5/A5_6") (pintype "bidirectional"))
    )
    (net (code "91") (name "unconnected-(U1-P6.6{slash}CB6{slash}A6-Pad7)") (class "Default")
      (node (ref "U1") (pin "7") (pinfunction "P6.6/CB6/A6_7") (pintype "bidirectional"))
    )
    (net (code "92") (name "unconnected-(U1-P6.7{slash}CB7{slash}A7-Pad8)") (class "Default")
      (node (ref "U1") (pin "8") (pinfunction "P6.7/CB7/A7_8") (pintype "bidirectional"))
    )
    (net (code "93") (name "unconnected-(U4-NC-Pad22)") (class "Default")
      (node (ref "U4") (pin "22") (pinfunction "NC_22") (pintype "bidirectional"))
    )
    (net (code "94") (name "unconnected-(U6-NC-Pad22)") (class "Default")
      (node (ref "U6") (pin "22") (pinfunction "NC_22") (pintype "bidirectional"))
    )
    (net (code "95") (name "~{FAULT_1}") (class "Default")
      (node (ref "R23") (pin "2") (pinfunction "2_2") (pintype "passive"))
      (node (ref "U4") (pin "18") (pinfunction "~{FAULT}_18") (pintype "bidirectional"))
    )
    (net (code "96") (name "~{FAULT_2}") (class "Default")
      (node (ref "R29") (pin "2") (pinfunction "2_2") (pintype "passive"))
      (node (ref "U6") (pin "18") (pinfunction "~{FAULT}_18") (pintype "bidirectional"))
    )
    (net (code "97") (name "~{RESET}") (class "Default")
      (node (ref "U1") (pin "25") (pinfunction "P1.7/TA1.0_25") (pintype "bidirectional"))
      (node (ref "U4") (pin "16") (pinfunction "~{RESET}_16") (pintype "bidirectional"))
      (node (ref "U6") (pin "16") (pinfunction "~{RESET}_16") (pintype "bidirectional"))
    )
    (net (code "98") (name "~{SLEEP_1}") (class "Default")
      (node (ref "R22") (pin "2") (pinfunction "2_2") (pintype "passive"))
      (node (ref "U4") (pin "17") (pinfunction "~{SLEEP}_17") (pintype "bidirectional"))
    )
    (net (code "99") (name "~{SLEEP_2}") (class "Default")
      (node (ref "R28") (pin "2") (pinfunction "2_2") (pintype "passive"))
      (node (ref "U6") (pin "17") (pinfunction "~{SLEEP}_17") (pintype "bidirectional"))
    )
  )
)
